# GPS_radiologger_v13.net
KiCad netlist of a schematic drawn in EAGLE
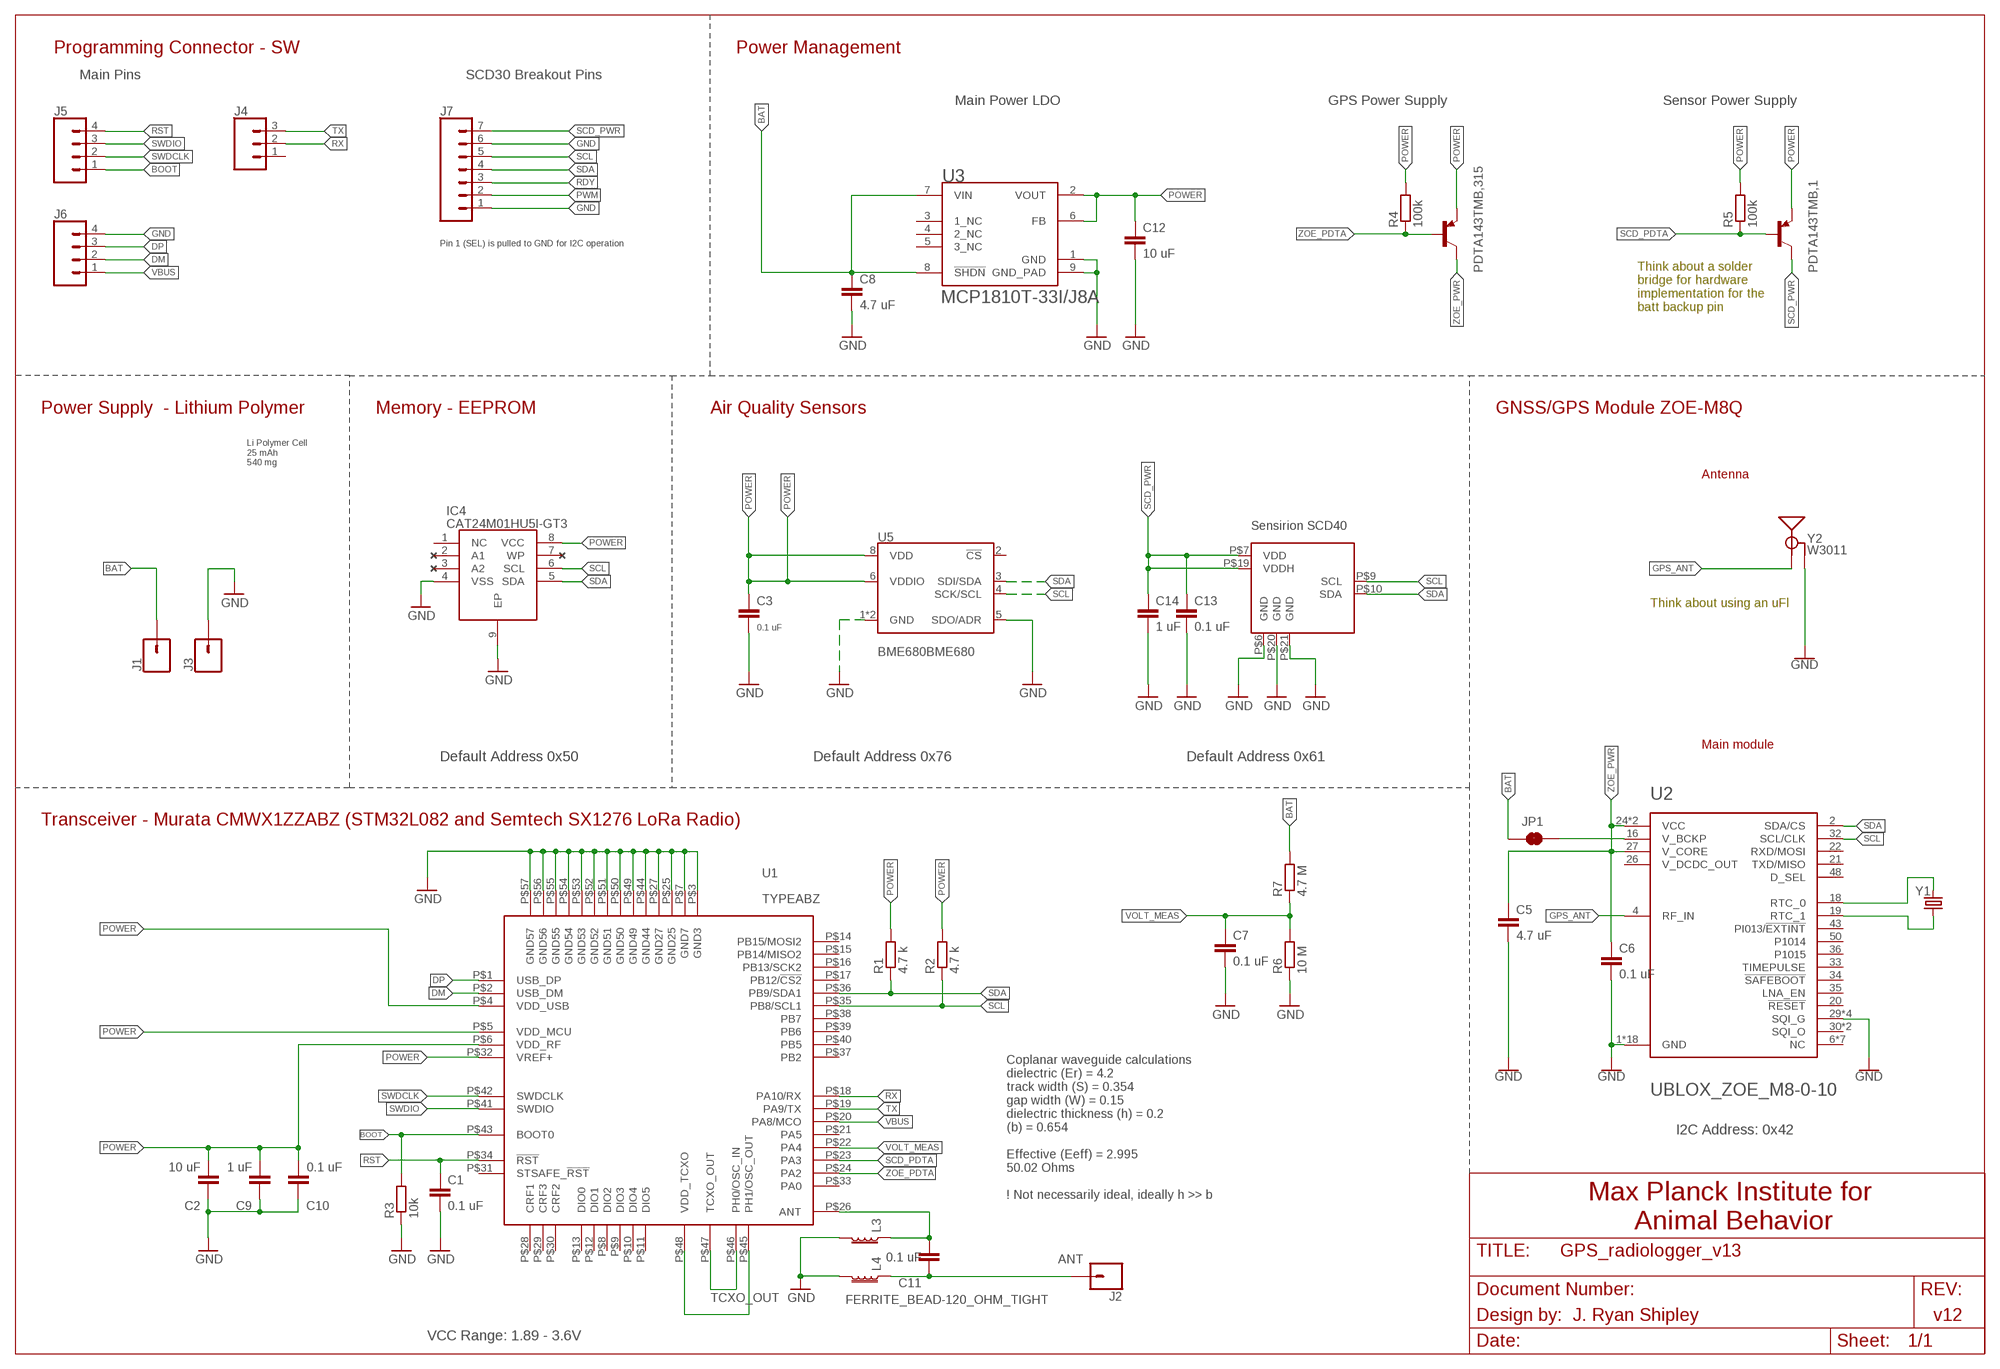
[diagram p0: schematic, sheet 1]

(export (version "E")
  (design (tool "Eeschema 10.0.6"))
  (components
    (comp (ref "C1")
      (value "0.1 uF")
      (footprint "eagle-import:C0201")
      (libsource (lib "eagle-import") (part "C-EUC0201"))
    )
    (comp (ref "C2")
      (value "10 uF")
      (footprint "eagle-import:C0201")
      (libsource (lib "eagle-import") (part "C-EUC0201"))
    )
    (comp (ref "C3")
      (value "0.1 uF")
      (footprint "eagle-import:C0201")
      (libsource (lib "eagle-import") (part "C-EUC0201"))
    )
    (comp (ref "C5")
      (value "4.7 uF")
      (footprint "eagle-import:C0201")
      (libsource (lib "eagle-import") (part "C-EUC0201"))
    )
    (comp (ref "C6")
      (value "0.1 uF")
      (footprint "eagle-import:C0201")
      (libsource (lib "eagle-import") (part "C-EUC0201"))
    )
    (comp (ref "C7")
      (value "0.1 uF")
      (footprint "eagle-import:C0201")
      (libsource (lib "eagle-import") (part "C-EUC0201"))
    )
    (comp (ref "C8")
      (value "4.7 uF")
      (footprint "eagle-import:C0201")
      (libsource (lib "eagle-import") (part "C-EUC0201"))
    )
    (comp (ref "C9")
      (value "1 uF")
      (footprint "eagle-import:C0201")
      (libsource (lib "eagle-import") (part "C-EUC0201"))
    )
    (comp (ref "C10")
      (value "0.1 uF")
      (footprint "eagle-import:C0201")
      (libsource (lib "eagle-import") (part "C-EUC0201"))
    )
    (comp (ref "C11")
      (value "0.1 uF")
      (footprint "eagle-import:C0201")
      (libsource (lib "eagle-import") (part "C-EUC0201"))
    )
    (comp (ref "C12")
      (value "10 uF")
      (footprint "eagle-import:C0201")
      (libsource (lib "eagle-import") (part "C-EUC0201"))
    )
    (comp (ref "C13")
      (value "0.1 uF")
      (footprint "eagle-import:C0201")
      (libsource (lib "eagle-import") (part "C-EUC0201"))
    )
    (comp (ref "C14")
      (value "1 uF")
      (footprint "eagle-import:C0201")
      (libsource (lib "eagle-import") (part "C-EUC0201"))
    )
    (comp (ref "IC4")
      (value "CAT24M01HU5I-GT3")
      (footprint "eagle-import:SON50P300X200X55-9N")
      (fields
        (field (name "MOUSER_PART_NUMBER") "863-CAT24M01HU5I-GT3")
        (field (name "RS_PART_NUMBER") "7814831P")
      )
      (libsource (lib "eagle-import") (part "CAT24M01HU5I-GT3"))
    )
    (comp (ref "J1")
      (value "CONN_01PTH_NO_SILK_YES_STOP")
      (footprint "eagle-import:1X01_NO_SILK")
      (libsource (lib "eagle-import") (part "CONN_01PTH_NO_SILK_YES_STOP"))
    )
    (comp (ref "J2")
      (value "CONN_01PTH_NO_SILK_SMALL")
      (footprint "eagle-import:1X01_SMALL")
      (libsource (lib "eagle-import") (part "CONN_01PTH_NO_SILK_SMALL"))
    )
    (comp (ref "J3")
      (value "CONN_01PTH_NO_SILK_YES_STOP")
      (footprint "eagle-import:1X01_NO_SILK")
      (libsource (lib "eagle-import") (part "CONN_01PTH_NO_SILK_YES_STOP"))
    )
    (comp (ref "J4")
      (value "CONN_031X03_1.27_NO_SILK")
      (footprint "eagle-import:1X03_1.27MM_NO_SILK")
      (libsource (lib "eagle-import") (part "CONN_031X03_1.27_NO_SILK"))
    )
    (comp (ref "J5")
      (value "CONN_041.27MM_NO_SILK")
      (footprint "eagle-import:1X04_1.27MM_NO_SILK")
      (libsource (lib "eagle-import") (part "CONN_041.27MM_NO_SILK"))
    )
    (comp (ref "J6")
      (value "CONN_041.27MM_NO_SILK")
      (footprint "eagle-import:1X04_1.27MM_NO_SILK")
      (libsource (lib "eagle-import") (part "CONN_041.27MM_NO_SILK"))
    )
    (comp (ref "J7")
      (value "CONN_07NO_SILK")
      (footprint "eagle-import:1X07_NO_SILK")
      (libsource (lib "eagle-import") (part "CONN_07NO_SILK"))
    )
    (comp (ref "JP1")
      (value "JUMPER-SMT_2_NC_TRACE_NO-SILK")
      (footprint "eagle-import:SMT-JUMPER_2_NC_TRACE_NO-SILK")
      (libsource (lib "eagle-import") (part "JUMPER-SMT_2_NC_TRACE_NO-SILK"))
    )
    (comp (ref "L3")
      (value "FERRITE_BEAD-120_OHM_TIGHT")
      (footprint "eagle-import:0402-TIGHT")
      (libsource (lib "eagle-import") (part "FERRITE_BEAD-120_OHM_TIGHT"))
    )
    (comp (ref "L4")
      (value "FERRITE_BEAD-120_OHM_TIGHT")
      (footprint "eagle-import:0402-TIGHT")
      (libsource (lib "eagle-import") (part "FERRITE_BEAD-120_OHM_TIGHT"))
    )
    (comp (ref "PDTA143TMB,1")
      (value "TINYPICO-PNPAMB")
      (footprint "eagle-import:SOT883(B)")
      (libsource (lib "eagle-import") (part "TINYPICO-PNPMBA"))
    )
    (comp (ref "PDTA143TMB,315")
      (value "TINYPICO-PNPAMB")
      (footprint "eagle-import:SOT883(B)")
      (libsource (lib "eagle-import") (part "TINYPICO-PNPMBA"))
    )
    (comp (ref "R1")
      (value "4.7 k")
      (footprint "eagle-import:R0201")
      (libsource (lib "eagle-import") (part "R-EU_R0201"))
    )
    (comp (ref "R2")
      (value "4.7 k")
      (footprint "eagle-import:R0201")
      (libsource (lib "eagle-import") (part "R-EU_R0201"))
    )
    (comp (ref "R3")
      (value "10k")
      (footprint "eagle-import:R0201")
      (libsource (lib "eagle-import") (part "R-EU_R0201"))
    )
    (comp (ref "R4")
      (value "100k")
      (footprint "eagle-import:R0201")
      (libsource (lib "eagle-import") (part "R-EU_R0201"))
    )
    (comp (ref "R5")
      (value "100k")
      (footprint "eagle-import:R0201")
      (libsource (lib "eagle-import") (part "R-EU_R0201"))
    )
    (comp (ref "R6")
      (value "10 M")
      (footprint "eagle-import:R0201")
      (libsource (lib "eagle-import") (part "R-EU_R0201"))
    )
    (comp (ref "R7")
      (value "4.7 M")
      (footprint "eagle-import:R0201")
      (libsource (lib "eagle-import") (part "R-EU_R0201"))
    )
    (comp (ref "U$1")
      (value "SCD40")
      (footprint "eagle-import:SCD40_LGA")
      (libsource (lib "eagle-import") (part "SCD40"))
    )
    (comp (ref "U1")
      (value "TYPEABZ")
      (footprint "eagle-import:TYPEABZ")
      (libsource (lib "eagle-import") (part "TYPEABZ"))
    )
    (comp (ref "U2")
      (value "UBLOX_ZOE_M8-0-10")
      (footprint "eagle-import:UBLOX_ZOE_M8-0-10")
      (libsource (lib "eagle-import") (part "UBLOX_ZOE_M8-0-10"))
    )
    (comp (ref "U3")
      (value "MICROCHIP_MCP1810T-33I-J8AMICROCHIP_MCP1810T-33I-J8A_0_0")
      (footprint "eagle-import:MICROCHIP_MCP1810T-33I-J8A_0")
      (fields
        (field (name "DIGIKEY_PART_NUMBER") "MCP1810T-33I/J8ACT-ND")
        (field (name "MF") "Microchip")
        (field (name "MOUSER_PART_NUMBER") "579-MCP1810T-33I/J8A")
      )
      (libsource (lib "eagle-import") (part "MICROCHIP_MCP1810T-33I-J8AMICROCHIP_MCP1810T-33I-J8A_0_0"))
    )
    (comp (ref "U5")
      (value "BME680BME680")
      (footprint "eagle-import:LGA3.0X3.0")
      (libsource (lib "eagle-import") (part "BME680BME680"))
    )
    (comp (ref "Y1")
      (value "32.768kHz")
      (footprint "eagle-import:CRYSTAL-SMD-1.0X1.2MM")
      (libsource (lib "eagle-import") (part "CRYSTAL-32.768KHZ"))
    )
    (comp (ref "Y2")
      (value "W3011")
      (footprint "eagle-import:W3011")
      (libsource (lib "eagle-import") (part "GPS_CHIP_ANTENNAW3011"))
    )
  )
  (nets
    (net (code "1") (name "/ANT") (class "Default")
      (node (ref "C11") (pin "1") (pinfunction "1_1") (pintype "passive"))
      (node (ref "J2") (pin "P$1") (pinfunction "1_P$1") (pintype "passive"))
      (node (ref "L4") (pin "1") (pinfunction "1_1") (pintype "passive"))
    )
    (net (code "2") (name "/TCXO_OUT") (class "Default")
      (node (ref "U1") (pin "P$46") (pinfunction "PH0/OSC_IN_P$46") (pintype "bidirectional"))
      (node (ref "U1") (pin "P$47") (pinfunction "TCXO_OUT_P$47") (pintype "bidirectional"))
    )
    (net (code "3") (name "/V_DCDC_OUT") (class "Default")
      (node (ref "U2") (pin "26") (pinfunction "V_DCDC_OUT_26") (pintype "power_in"))
    )
    (net (code "4") (name "BAT") (class "Default")
      (node (ref "C8") (pin "1") (pinfunction "1_1") (pintype "passive"))
      (node (ref "J1") (pin "1") (pinfunction "1_1") (pintype "passive"))
      (node (ref "JP1") (pin "1") (pinfunction "1_1") (pintype "passive"))
      (node (ref "R7") (pin "2") (pinfunction "2_2") (pintype "passive"))
      (node (ref "U3") (pin "7") (pinfunction "VIN_7") (pintype "bidirectional"))
      (node (ref "U3") (pin "8") (pinfunction "~{SHDN}_8") (pintype "bidirectional"))
    )
    (net (code "5") (name "BOOT") (class "Default")
      (node (ref "J5") (pin "1") (pinfunction "1_1") (pintype "passive"))
      (node (ref "R3") (pin "2") (pinfunction "2_2") (pintype "passive"))
      (node (ref "U1") (pin "P$43") (pinfunction "BOOT0_P$43") (pintype "bidirectional"))
    )
    (net (code "6") (name "DM") (class "Default")
      (node (ref "J6") (pin "2") (pinfunction "2_2") (pintype "passive"))
      (node (ref "U1") (pin "P$2") (pinfunction "USB_DM_P$2") (pintype "bidirectional"))
    )
    (net (code "7") (name "DP") (class "Default")
      (node (ref "J6") (pin "3") (pinfunction "3_3") (pintype "passive"))
      (node (ref "U1") (pin "P$1") (pinfunction "USB_DP_P$1") (pintype "bidirectional"))
    )
    (net (code "8") (name "GND") (class "Default")
      (node (ref "C1") (pin "2") (pinfunction "2_2") (pintype "passive"))
      (node (ref "C10") (pin "1") (pinfunction "1_1") (pintype "passive"))
      (node (ref "C12") (pin "2") (pinfunction "2_2") (pintype "passive"))
      (node (ref "C13") (pin "2") (pinfunction "2_2") (pintype "passive"))
      (node (ref "C14") (pin "2") (pinfunction "2_2") (pintype "passive"))
      (node (ref "C2") (pin "1") (pinfunction "1_1") (pintype "passive"))
      (node (ref "C3") (pin "2") (pinfunction "2_2") (pintype "passive"))
      (node (ref "C5") (pin "2") (pinfunction "2_2") (pintype "passive"))
      (node (ref "C6") (pin "2") (pinfunction "2_2") (pintype "passive"))
      (node (ref "C7") (pin "2") (pinfunction "2_2") (pintype "passive"))
      (node (ref "C8") (pin "2") (pinfunction "2_2") (pintype "passive"))
      (node (ref "C9") (pin "1") (pinfunction "1_1") (pintype "passive"))
      (node (ref "IC4") (pin "4") (pinfunction "VSS_4") (pintype "power_in"))
      (node (ref "IC4") (pin "9") (pinfunction "EP_9") (pintype "bidirectional"))
      (node (ref "J3") (pin "1") (pinfunction "1_1") (pintype "passive"))
      (node (ref "J6") (pin "4") (pinfunction "4_4") (pintype "passive"))
      (node (ref "J7") (pin "1") (pinfunction "1_1") (pintype "passive"))
      (node (ref "J7") (pin "6") (pinfunction "6_6") (pintype "passive"))
      (node (ref "L3") (pin "2") (pinfunction "2_2") (pintype "passive"))
      (node (ref "L4") (pin "2") (pinfunction "2_2") (pintype "passive"))
      (node (ref "R3") (pin "1") (pinfunction "1_1") (pintype "passive"))
      (node (ref "R6") (pin "1") (pinfunction "1_1") (pintype "passive"))
      (node (ref "U$1") (pin "P$20") (pinfunction "GND_P$20") (pintype "bidirectional"))
      (node (ref "U$1") (pin "P$21") (pinfunction "GND_P$21") (pintype "bidirectional"))
      (node (ref "U$1") (pin "P$6") (pinfunction "GND_P$6") (pintype "bidirectional"))
      (node (ref "U1") (pin "P$25") (pinfunction "GND25_P$25") (pintype "power_in"))
      (node (ref "U1") (pin "P$27") (pinfunction "GND27_P$27") (pintype "power_in"))
      (node (ref "U1") (pin "P$3") (pinfunction "GND3_P$3") (pintype "power_in"))
      (node (ref "U1") (pin "P$44") (pinfunction "GND44_P$44") (pintype "power_in"))
      (node (ref "U1") (pin "P$49") (pinfunction "GND49_P$49") (pintype "power_in"))
      (node (ref "U1") (pin "P$50") (pinfunction "GND50_P$50") (pintype "power_in"))
      (node (ref "U1") (pin "P$51") (pinfunction "GND51_P$51") (pintype "power_in"))
      (node (ref "U1") (pin "P$52") (pinfunction "GND52_P$52") (pintype "power_in"))
      (node (ref "U1") (pin "P$53") (pinfunction "GND53_P$53") (pintype "power_in"))
      (node (ref "U1") (pin "P$54") (pinfunction "GND54_P$54") (pintype "power_in"))
      (node (ref "U1") (pin "P$55") (pinfunction "GND55_P$55") (pintype "power_in"))
      (node (ref "U1") (pin "P$56") (pinfunction "GND56_P$56") (pintype "power_in"))
      (node (ref "U1") (pin "P$57") (pinfunction "GND57_P$57") (pintype "power_in"))
      (node (ref "U1") (pin "P$7") (pinfunction "GND7_P$7") (pintype "power_in"))
      (node (ref "U2") (pin "1") (pinfunction "GND_1") (pintype "power_in"))
      (node (ref "U2") (pin "10") (pinfunction "GND_10") (pintype "power_in"))
      (node (ref "U2") (pin "11") (pinfunction "GND_11") (pintype "power_in"))
      (node (ref "U2") (pin "12") (pinfunction "GND_12") (pintype "power_in"))
      (node (ref "U2") (pin "17") (pinfunction "GND_17") (pintype "power_in"))
      (node (ref "U2") (pin "23") (pinfunction "GND_23") (pintype "power_in"))
      (node (ref "U2") (pin "29") (pinfunction "SQI_G_29") (pintype "bidirectional"))
      (node (ref "U2") (pin "3") (pinfunction "GND_3") (pintype "power_in"))
      (node (ref "U2") (pin "31") (pinfunction "SQI_G_31") (pintype "bidirectional"))
      (node (ref "U2") (pin "37") (pinfunction "GND_37") (pintype "power_in"))
      (node (ref "U2") (pin "38") (pinfunction "GND_38") (pintype "power_in"))
      (node (ref "U2") (pin "39") (pinfunction "GND_39") (pintype "power_in"))
      (node (ref "U2") (pin "40") (pinfunction "GND_40") (pintype "power_in"))
      (node (ref "U2") (pin "41") (pinfunction "GND_41") (pintype "power_in"))
      (node (ref "U2") (pin "44") (pinfunction "GND_44") (pintype "power_in"))
      (node (ref "U2") (pin "46") (pinfunction "SQI_G_46") (pintype "bidirectional"))
      (node (ref "U2") (pin "47") (pinfunction "SQI_G_47") (pintype "bidirectional"))
      (node (ref "U2") (pin "49") (pinfunction "GND_49") (pintype "power_in"))
      (node (ref "U2") (pin "5") (pinfunction "GND_5") (pintype "power_in"))
      (node (ref "U2") (pin "7") (pinfunction "GND_7") (pintype "power_in"))
      (node (ref "U2") (pin "8") (pinfunction "GND_8") (pintype "power_in"))
      (node (ref "U2") (pin "9") (pinfunction "GND_9") (pintype "power_in"))
      (node (ref "U3") (pin "1") (pinfunction "GND_1") (pintype "bidirectional"))
      (node (ref "U3") (pin "9") (pinfunction "GND_PAD_9") (pintype "bidirectional"))
      (node (ref "U5") (pin "1") (pinfunction "GND_1") (pintype "bidirectional"))
      (node (ref "U5") (pin "5") (pinfunction "SDO/ADR_5") (pintype "bidirectional"))
      (node (ref "U5") (pin "7") (pinfunction "GND_7") (pintype "bidirectional"))
      (node (ref "Y2") (pin "2") (pinfunction "GND_2") (pintype "bidirectional"))
      (node (ref "Y2") (pin "3") (pinfunction "GND_3") (pintype "bidirectional"))
    )
    (net (code "9") (name "GPS_ANT") (class "Default")
      (node (ref "U2") (pin "4") (pinfunction "RF_IN_4") (pintype "bidirectional"))
      (node (ref "Y2") (pin "1") (pinfunction "SIGNAL_1") (pintype "bidirectional"))
    )
    (net (code "10") (name "Net-(U1-ANT)") (class "Default")
      (node (ref "C11") (pin "2") (pinfunction "2_2") (pintype "passive"))
      (node (ref "L3") (pin "1") (pinfunction "1_1") (pintype "passive"))
      (node (ref "U1") (pin "P$26") (pinfunction "ANT_P$26") (pintype "bidirectional"))
    )
    (net (code "11") (name "Net-(U1-PH1{slash}OSC_OUT)") (class "Default")
      (node (ref "U1") (pin "P$45") (pinfunction "PH1/OSC_OUT_P$45") (pintype "bidirectional"))
      (node (ref "U1") (pin "P$48") (pinfunction "VDD_TCXO_P$48") (pintype "power_in"))
    )
    (net (code "12") (name "Net-(U2-RTC_0)") (class "Default")
      (node (ref "U2") (pin "18") (pinfunction "RTC_0_18") (pintype "bidirectional"))
      (node (ref "Y1") (pin "P$2") (pinfunction "2_P$2") (pintype "passive"))
    )
    (net (code "13") (name "Net-(U2-RTC_1)") (class "Default")
      (node (ref "U2") (pin "19") (pinfunction "RTC_1_19") (pintype "bidirectional"))
      (node (ref "Y1") (pin "P$1") (pinfunction "1_P$1") (pintype "passive"))
    )
    (net (code "14") (name "Net-(U2-V_BCKP)") (class "Default")
      (node (ref "JP1") (pin "2") (pinfunction "2_2") (pintype "passive"))
      (node (ref "U2") (pin "16") (pinfunction "V_BCKP_16") (pintype "power_in"))
    )
    (net (code "15") (name "POWER") (class "Default")
      (node (ref "C10") (pin "2") (pinfunction "2_2") (pintype "passive"))
      (node (ref "C12") (pin "1") (pinfunction "1_1") (pintype "passive"))
      (node (ref "C2") (pin "2") (pinfunction "2_2") (pintype "passive"))
      (node (ref "C3") (pin "1") (pinfunction "1_1") (pintype "passive"))
      (node (ref "C9") (pin "2") (pinfunction "2_2") (pintype "passive"))
      (node (ref "IC4") (pin "8") (pinfunction "VCC_8") (pintype "power_in"))
      (node (ref "PDTA143TMB,1") (pin "2") (pinfunction "E_2") (pintype "passive"))
      (node (ref "PDTA143TMB,315") (pin "2") (pinfunction "E_2") (pintype "passive"))
      (node (ref "R1") (pin "2") (pinfunction "2_2") (pintype "passive"))
      (node (ref "R2") (pin "2") (pinfunction "2_2") (pintype "passive"))
      (node (ref "R4") (pin "2") (pinfunction "2_2") (pintype "passive"))
      (node (ref "R5") (pin "2") (pinfunction "2_2") (pintype "passive"))
      (node (ref "U1") (pin "P$32") (pinfunction "VREF+_P$32") (pintype "power_in"))
      (node (ref "U1") (pin "P$4") (pinfunction "VDD_USB_P$4") (pintype "power_in"))
      (node (ref "U1") (pin "P$5") (pinfunction "VDD_MCU_P$5") (pintype "power_in"))
      (node (ref "U1") (pin "P$6") (pinfunction "VDD_RF_P$6") (pintype "power_in"))
      (node (ref "U3") (pin "2") (pinfunction "VOUT_2") (pintype "bidirectional"))
      (node (ref "U3") (pin "6") (pinfunction "FB_6") (pintype "bidirectional"))
      (node (ref "U5") (pin "6") (pinfunction "VDDIO_6") (pintype "bidirectional"))
      (node (ref "U5") (pin "8") (pinfunction "VDD_8") (pintype "bidirectional"))
    )
    (net (code "16") (name "PWM") (class "Default")
      (node (ref "J7") (pin "2") (pinfunction "2_2") (pintype "passive"))
    )
    (net (code "17") (name "RDY") (class "Default")
      (node (ref "J7") (pin "3") (pinfunction "3_3") (pintype "passive"))
    )
    (net (code "18") (name "RST") (class "Default")
      (node (ref "C1") (pin "1") (pinfunction "1_1") (pintype "passive"))
      (node (ref "J5") (pin "4") (pinfunction "4_4") (pintype "passive"))
      (node (ref "U1") (pin "P$34") (pinfunction "~{RST}_P$34") (pintype "bidirectional"))
    )
    (net (code "19") (name "RX") (class "Default")
      (node (ref "J4") (pin "2") (pinfunction "2_2") (pintype "passive"))
      (node (ref "U1") (pin "P$18") (pinfunction "PA10/RX_P$18") (pintype "bidirectional"))
    )
    (net (code "20") (name "SCD_PDTA") (class "Default")
      (node (ref "PDTA143TMB,1") (pin "1") (pinfunction "B_1") (pintype "passive"))
      (node (ref "R5") (pin "1") (pinfunction "1_1") (pintype "passive"))
      (node (ref "U1") (pin "P$23") (pinfunction "PA3_P$23") (pintype "bidirectional"))
    )
    (net (code "21") (name "SCD_PWR") (class "Default")
      (node (ref "C13") (pin "1") (pinfunction "1_1") (pintype "passive"))
      (node (ref "C14") (pin "1") (pinfunction "1_1") (pintype "passive"))
      (node (ref "J7") (pin "7") (pinfunction "7_7") (pintype "passive"))
      (node (ref "PDTA143TMB,1") (pin "3") (pinfunction "C_3") (pintype "passive"))
      (node (ref "U$1") (pin "P$19") (pinfunction "VDDH_P$19") (pintype "bidirectional"))
      (node (ref "U$1") (pin "P$7") (pinfunction "VDD_P$7") (pintype "bidirectional"))
    )
    (net (code "22") (name "SCL") (class "Default")
      (node (ref "IC4") (pin "6") (pinfunction "SCL_6") (pintype "bidirectional"))
      (node (ref "J7") (pin "5") (pinfunction "5_5") (pintype "passive"))
      (node (ref "R2") (pin "1") (pinfunction "1_1") (pintype "passive"))
      (node (ref "U$1") (pin "P$9") (pinfunction "SCL_P$9") (pintype "bidirectional"))
      (node (ref "U1") (pin "P$35") (pinfunction "PB8/SCL1_P$35") (pintype "bidirectional"))
      (node (ref "U2") (pin "32") (pinfunction "SCL/CLK_32") (pintype "bidirectional"))
      (node (ref "U5") (pin "4") (pinfunction "SCK/SCL_4") (pintype "bidirectional"))
    )
    (net (code "23") (name "SDA") (class "Default")
      (node (ref "IC4") (pin "5") (pinfunction "SDA_5") (pintype "bidirectional"))
      (node (ref "J7") (pin "4") (pinfunction "4_4") (pintype "passive"))
      (node (ref "R1") (pin "1") (pinfunction "1_1") (pintype "passive"))
      (node (ref "U$1") (pin "P$10") (pinfunction "SDA_P$10") (pintype "bidirectional"))
      (node (ref "U1") (pin "P$36") (pinfunction "PB9/SDA1_P$36") (pintype "bidirectional"))
      (node (ref "U2") (pin "2") (pinfunction "SDA/CS_2") (pintype "bidirectional"))
      (node (ref "U5") (pin "3") (pinfunction "SDI/SDA_3") (pintype "bidirectional"))
    )
    (net (code "24") (name "SWDCLK") (class "Default")
      (node (ref "J5") (pin "2") (pinfunction "2_2") (pintype "passive"))
      (node (ref "U1") (pin "P$42") (pinfunction "SWDCLK_P$42") (pintype "bidirectional"))
    )
    (net (code "25") (name "SWDIO") (class "Default")
      (node (ref "J5") (pin "3") (pinfunction "3_3") (pintype "passive"))
      (node (ref "U1") (pin "P$41") (pinfunction "SWDIO_P$41") (pintype "bidirectional"))
    )
    (net (code "26") (name "TX") (class "Default")
      (node (ref "J4") (pin "3") (pinfunction "3_3") (pintype "passive"))
      (node (ref "U1") (pin "P$19") (pinfunction "PA9/TX_P$19") (pintype "bidirectional"))
    )
    (net (code "27") (name "VBUS") (class "Default")
      (node (ref "J6") (pin "1") (pinfunction "1_1") (pintype "passive"))
      (node (ref "U1") (pin "P$20") (pinfunction "PA8/MCO_P$20") (pintype "bidirectional"))
    )
    (net (code "28") (name "VOLT_MEAS") (class "Default")
      (node (ref "C7") (pin "1") (pinfunction "1_1") (pintype "passive"))
      (node (ref "R6") (pin "2") (pinfunction "2_2") (pintype "passive"))
      (node (ref "R7") (pin "1") (pinfunction "1_1") (pintype "passive"))
      (node (ref "U1") (pin "P$22") (pinfunction "PA4_P$22") (pintype "bidirectional"))
    )
    (net (code "29") (name "ZOE_PDTA") (class "Default")
      (node (ref "PDTA143TMB,315") (pin "1") (pinfunction "B_1") (pintype "passive"))
      (node (ref "R4") (pin "1") (pinfunction "1_1") (pintype "passive"))
      (node (ref "U1") (pin "P$24") (pinfunction "PA2_P$24") (pintype "bidirectional"))
    )
    (net (code "30") (name "ZOE_PWR") (class "Default")
      (node (ref "C5") (pin "1") (pinfunction "1_1") (pintype "passive"))
      (node (ref "C6") (pin "1") (pinfunction "1_1") (pintype "passive"))
      (node (ref "PDTA143TMB,315") (pin "3") (pinfunction "C_3") (pintype "passive"))
      (node (ref "U2") (pin "24") (pinfunction "VCC_24") (pintype "power_in"))
      (node (ref "U2") (pin "25") (pinfunction "VCC_25") (pintype "power_in"))
      (node (ref "U2") (pin "27") (pinfunction "V_CORE_27") (pintype "power_in"))
    )
    (net (code "31") (name "unconnected-(IC4-A1-Pad2)") (class "Default")
      (node (ref "IC4") (pin "2") (pinfunction "A1_2") (pintype "bidirectional"))
    )
    (net (code "32") (name "unconnected-(IC4-A2-Pad3)") (class "Default")
      (node (ref "IC4") (pin "3") (pinfunction "A2_3") (pintype "bidirectional"))
    )
    (net (code "33") (name "unconnected-(IC4-NC-Pad1)") (class "Default")
      (node (ref "IC4") (pin "1") (pinfunction "NC_1") (pintype "no_connect"))
    )
    (net (code "34") (name "unconnected-(IC4-WP-Pad7)") (class "Default")
      (node (ref "IC4") (pin "7") (pinfunction "WP_7") (pintype "bidirectional"))
    )
    (net (code "35") (name "unconnected-(J4-Pad1)") (class "Default")
      (node (ref "J4") (pin "1") (pinfunction "1_1") (pintype "passive"))
    )
    (net (code "36") (name "unconnected-(U1-CRF1-PadP$28)") (class "Default")
      (node (ref "U1") (pin "P$28") (pinfunction "CRF1_P$28") (pintype "no_connect"))
    )
    (net (code "37") (name "unconnected-(U1-CRF2-PadP$30)") (class "Default")
      (node (ref "U1") (pin "P$30") (pinfunction "CRF2_P$30") (pintype "no_connect"))
    )
    (net (code "38") (name "unconnected-(U1-CRF3-PadP$29)") (class "Default")
      (node (ref "U1") (pin "P$29") (pinfunction "CRF3_P$29") (pintype "no_connect"))
    )
    (net (code "39") (name "unconnected-(U1-DIO0-PadP$13)") (class "Default")
      (node (ref "U1") (pin "P$13") (pinfunction "DIO0_P$13") (pintype "no_connect"))
    )
    (net (code "40") (name "unconnected-(U1-DIO1-PadP$12)") (class "Default")
      (node (ref "U1") (pin "P$12") (pinfunction "DIO1_P$12") (pintype "no_connect"))
    )
    (net (code "41") (name "unconnected-(U1-DIO2-PadP$8)") (class "Default")
      (node (ref "U1") (pin "P$8") (pinfunction "DIO2_P$8") (pintype "no_connect"))
    )
    (net (code "42") (name "unconnected-(U1-DIO3-PadP$9)") (class "Default")
      (node (ref "U1") (pin "P$9") (pinfunction "DIO3_P$9") (pintype "no_connect"))
    )
    (net (code "43") (name "unconnected-(U1-DIO4-PadP$10)") (class "Default")
      (node (ref "U1") (pin "P$10") (pinfunction "DIO4_P$10") (pintype "bidirectional"))
    )
    (net (code "44") (name "unconnected-(U1-DIO5-PadP$11)") (class "Default")
      (node (ref "U1") (pin "P$11") (pinfunction "DIO5_P$11") (pintype "bidirectional"))
    )
    (net (code "45") (name "unconnected-(U1-PA0-PadP$33)") (class "Default")
      (node (ref "U1") (pin "P$33") (pinfunction "PA0_P$33") (pintype "bidirectional"))
    )
    (net (code "46") (name "unconnected-(U1-PA5-PadP$21)") (class "Default")
      (node (ref "U1") (pin "P$21") (pinfunction "PA5_P$21") (pintype "bidirectional"))
    )
    (net (code "47") (name "unconnected-(U1-PB2-PadP$37)") (class "Default")
      (node (ref "U1") (pin "P$37") (pinfunction "PB2_P$37") (pintype "bidirectional"))
    )
    (net (code "48") (name "unconnected-(U1-PB5-PadP$40)") (class "Default")
      (node (ref "U1") (pin "P$40") (pinfunction "PB5_P$40") (pintype "bidirectional"))
    )
    (net (code "49") (name "unconnected-(U1-PB6-PadP$39)") (class "Default")
      (node (ref "U1") (pin "P$39") (pinfunction "PB6_P$39") (pintype "bidirectional"))
    )
    (net (code "50") (name "unconnected-(U1-PB7-PadP$38)") (class "Default")
      (node (ref "U1") (pin "P$38") (pinfunction "PB7_P$38") (pintype "bidirectional"))
    )
    (net (code "51") (name "unconnected-(U1-PB12{slash}~{CS2}-PadP$17)") (class "Default")
      (node (ref "U1") (pin "P$17") (pinfunction "PB12/~{CS2}_P$17") (pintype "bidirectional"))
    )
    (net (code "52") (name "unconnected-(U1-PB13{slash}SCK2-PadP$16)") (class "Default")
      (node (ref "U1") (pin "P$16") (pinfunction "PB13/SCK2_P$16") (pintype "bidirectional"))
    )
    (net (code "53") (name "unconnected-(U1-PB14{slash}MISO2-PadP$15)") (class "Default")
      (node (ref "U1") (pin "P$15") (pinfunction "PB14/MISO2_P$15") (pintype "bidirectional"))
    )
    (net (code "54") (name "unconnected-(U1-PB15{slash}MOSI2-PadP$14)") (class "Default")
      (node (ref "U1") (pin "P$14") (pinfunction "PB15/MOSI2_P$14") (pintype "bidirectional"))
    )
    (net (code "55") (name "unconnected-(U1-STSAFE_~{RST}-PadP$31)") (class "Default")
      (node (ref "U1") (pin "P$31") (pinfunction "STSAFE_~{RST}_P$31") (pintype "bidirectional"))
    )
    (net (code "56") (name "unconnected-(U2-D_SEL-Pad48)") (class "Default")
      (node (ref "U2") (pin "48") (pinfunction "D_SEL_48") (pintype "bidirectional"))
    )
    (net (code "57") (name "unconnected-(U2-LNA_EN-Pad35)") (class "Default")
      (node (ref "U2") (pin "35") (pinfunction "LNA_EN_35") (pintype "bidirectional"))
    )
    (net (code "58") (name "unconnected-(U2-NC-Pad6)") (class "Default")
      (node (ref "U2") (pin "6") (pinfunction "NC_6") (pintype "no_connect"))
    )
    (net (code "59") (name "unconnected-(U2-NC-Pad13)") (class "Default")
      (node (ref "U2") (pin "13") (pinfunction "NC_13") (pintype "no_connect"))
    )
    (net (code "60") (name "unconnected-(U2-NC-Pad14)") (class "Default")
      (node (ref "U2") (pin "14") (pinfunction "NC_14") (pintype "no_connect"))
    )
    (net (code "61") (name "unconnected-(U2-NC-Pad15)") (class "Default")
      (node (ref "U2") (pin "15") (pinfunction "NC_15") (pintype "no_connect"))
    )
    (net (code "62") (name "unconnected-(U2-NC-Pad28)") (class "Default")
      (node (ref "U2") (pin "28") (pinfunction "NC_28") (pintype "no_connect"))
    )
    (net (code "63") (name "unconnected-(U2-NC-Pad42)") (class "Default")
      (node (ref "U2") (pin "42") (pinfunction "NC_42") (pintype "no_connect"))
    )
    (net (code "64") (name "unconnected-(U2-NC-Pad51)") (class "Default")
      (node (ref "U2") (pin "51") (pinfunction "NC_51") (pintype "no_connect"))
    )
    (net (code "65") (name "unconnected-(U2-P1014-Pad50)") (class "Default")
      (node (ref "U2") (pin "50") (pinfunction "P1014_50") (pintype "bidirectional"))
    )
    (net (code "66") (name "unconnected-(U2-P1015-Pad36)") (class "Default")
      (node (ref "U2") (pin "36") (pinfunction "P1015_36") (pintype "bidirectional"))
    )
    (net (code "67") (name "unconnected-(U2-PI013{slash}~{EXTINT}-Pad43)") (class "Default")
      (node (ref "U2") (pin "43") (pinfunction "PI013/~{EXTINT}_43") (pintype "bidirectional"))
    )
    (net (code "68") (name "unconnected-(U2-RXD{slash}MOSI-Pad22)") (class "Default")
      (node (ref "U2") (pin "22") (pinfunction "RXD/MOSI_22") (pintype "bidirectional"))
    )
    (net (code "69") (name "unconnected-(U2-SQI_O-Pad30)") (class "Default")
      (node (ref "U2") (pin "30") (pinfunction "SQI_O_30") (pintype "no_connect"))
    )
    (net (code "70") (name "unconnected-(U2-SQI_O-Pad45)") (class "Default")
      (node (ref "U2") (pin "45") (pinfunction "SQI_O_45") (pintype "no_connect"))
    )
    (net (code "71") (name "unconnected-(U2-TIMEPULSE-Pad33)") (class "Default")
      (node (ref "U2") (pin "33") (pinfunction "TIMEPULSE_33") (pintype "bidirectional"))
    )
    (net (code "72") (name "unconnected-(U2-TXD{slash}MISO-Pad21)") (class "Default")
      (node (ref "U2") (pin "21") (pinfunction "TXD/MISO_21") (pintype "bidirectional"))
    )
    (net (code "73") (name "unconnected-(U2-~{RESET}-Pad20)") (class "Default")
      (node (ref "U2") (pin "20") (pinfunction "~{RESET}_20") (pintype "bidirectional"))
    )
    (net (code "74") (name "unconnected-(U2-~{SAFEBOOT}-Pad34)") (class "Default")
      (node (ref "U2") (pin "34") (pinfunction "~{SAFEBOOT}_34") (pintype "bidirectional"))
    )
    (net (code "75") (name "unconnected-(U3-1_NC-Pad3)") (class "Default")
      (node (ref "U3") (pin "3") (pinfunction "1_NC_3") (pintype "bidirectional"))
    )
    (net (code "76") (name "unconnected-(U3-2_NC-Pad4)") (class "Default")
      (node (ref "U3") (pin "4") (pinfunction "2_NC_4") (pintype "bidirectional"))
    )
    (net (code "77") (name "unconnected-(U3-3_NC-Pad5)") (class "Default")
      (node (ref "U3") (pin "5") (pinfunction "3_NC_5") (pintype "bidirectional"))
    )
    (net (code "78") (name "unconnected-(U5-~{CS}-Pad2)") (class "Default")
      (node (ref "U5") (pin "2") (pinfunction "~{CS}_2") (pintype "bidirectional"))
    )
  )
)
